# I2C_Line_Sensor.net
KiCad netlist of a schematic drawn in EAGLE
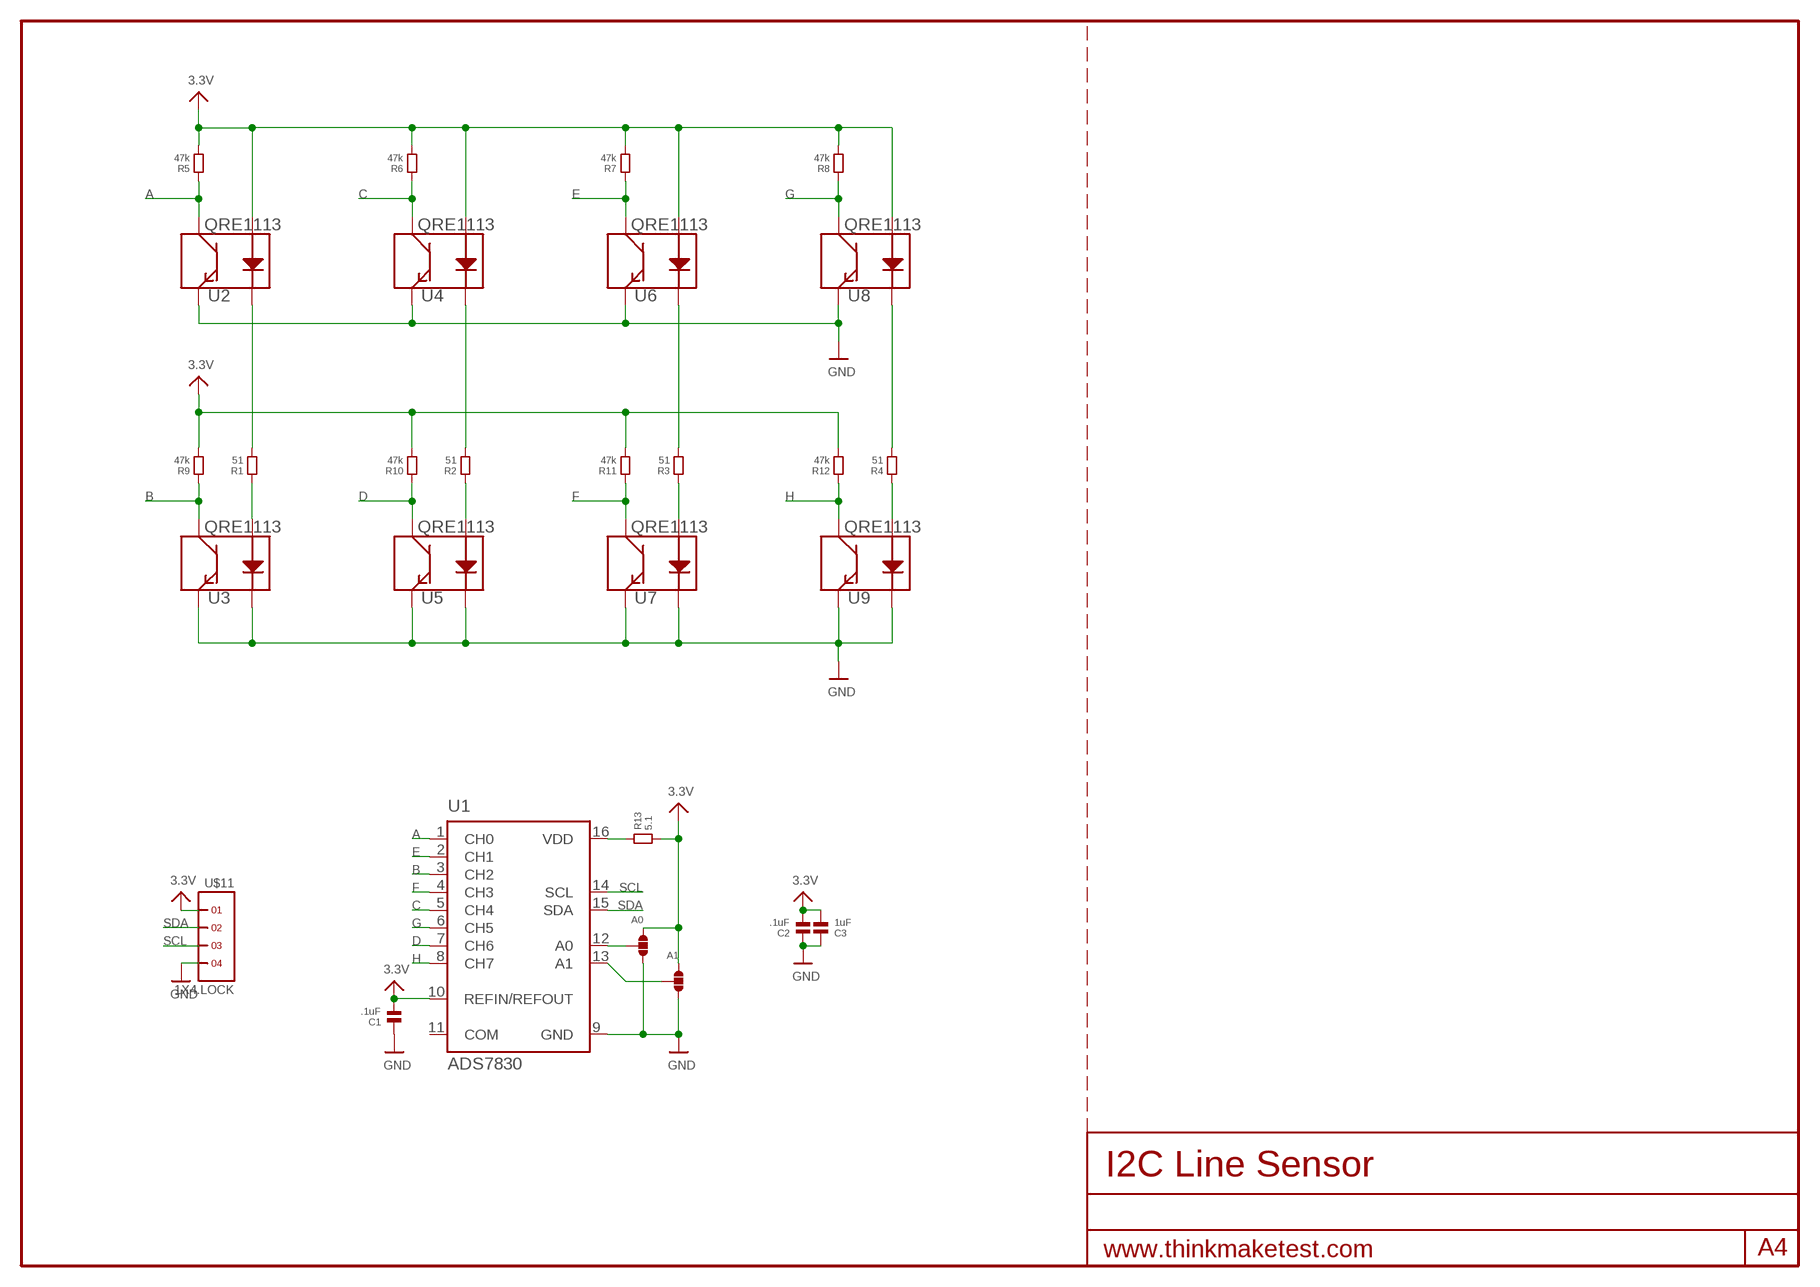
[diagram p0: schematic, sheet 1]

(export (version "E")
  (design (tool "Eeschema 10.0.6"))
  (components
    (comp (ref "A0")
      (value "SOLDERJUMPER.3.LRG.23")
      (footprint "eagle-import:3.LRG.23")
      (libsource (lib "eagle-import") (part "SOLDERJUMPER.3.LRG.23"))
    )
    (comp (ref "A1")
      (value "SOLDERJUMPER.3.LRG.23")
      (footprint "eagle-import:3.LRG.23")
      (libsource (lib "eagle-import") (part "SOLDERJUMPER.3.LRG.23"))
    )
    (comp (ref "C1")
      (value ".1uF")
      (footprint "eagle-import:0603")
      (libsource (lib "eagle-import") (part "CAPACITOR.0603"))
    )
    (comp (ref "C2")
      (value ".1uF")
      (footprint "eagle-import:0603")
      (libsource (lib "eagle-import") (part "CAPACITOR.0603"))
    )
    (comp (ref "C3")
      (value "1uF")
      (footprint "eagle-import:0603")
      (libsource (lib "eagle-import") (part "CAPACITOR.0603"))
    )
    (comp (ref "R1")
      (value "51")
      (footprint "eagle-import:0603")
      (libsource (lib "eagle-import") (part "RESISTOR.0603"))
    )
    (comp (ref "R2")
      (value "51")
      (footprint "eagle-import:0603")
      (libsource (lib "eagle-import") (part "RESISTOR.0603"))
    )
    (comp (ref "R3")
      (value "51")
      (footprint "eagle-import:0603")
      (libsource (lib "eagle-import") (part "RESISTOR.0603"))
    )
    (comp (ref "R4")
      (value "51")
      (footprint "eagle-import:0603")
      (libsource (lib "eagle-import") (part "RESISTOR.0603"))
    )
    (comp (ref "R5")
      (value "47k")
      (footprint "eagle-import:0603")
      (libsource (lib "eagle-import") (part "RESISTOR.0603"))
    )
    (comp (ref "R6")
      (value "47k")
      (footprint "eagle-import:0603")
      (libsource (lib "eagle-import") (part "RESISTOR.0603"))
    )
    (comp (ref "R7")
      (value "47k")
      (footprint "eagle-import:0603")
      (libsource (lib "eagle-import") (part "RESISTOR.0603"))
    )
    (comp (ref "R8")
      (value "47k")
      (footprint "eagle-import:0603")
      (libsource (lib "eagle-import") (part "RESISTOR.0603"))
    )
    (comp (ref "R9")
      (value "47k")
      (footprint "eagle-import:0603")
      (libsource (lib "eagle-import") (part "RESISTOR.0603"))
    )
    (comp (ref "R10")
      (value "47k")
      (footprint "eagle-import:0603")
      (libsource (lib "eagle-import") (part "RESISTOR.0603"))
    )
    (comp (ref "R11")
      (value "47k")
      (footprint "eagle-import:0603")
      (libsource (lib "eagle-import") (part "RESISTOR.0603"))
    )
    (comp (ref "R12")
      (value "47k")
      (footprint "eagle-import:0603")
      (libsource (lib "eagle-import") (part "RESISTOR.0603"))
    )
    (comp (ref "R13")
      (value "5.1")
      (footprint "eagle-import:0603")
      (libsource (lib "eagle-import") (part "RESISTOR.0603"))
    )
    (comp (ref "U$11")
      (value "1X4.LOCK")
      (footprint "eagle-import:1X4.LOCK")
      (libsource (lib "eagle-import") (part "1X4.LOCK"))
    )
    (comp (ref "U1")
      (value "ADS7830")
      (footprint "eagle-import:TSSOP16-PW")
      (libsource (lib "eagle-import") (part "ADS7828"))
    )
    (comp (ref "U2")
      (value "QRE1113")
      (footprint "eagle-import:QRE1113")
      (libsource (lib "eagle-import") (part "QRE1113"))
    )
    (comp (ref "U3")
      (value "QRE1113")
      (footprint "eagle-import:QRE1113")
      (libsource (lib "eagle-import") (part "QRE1113"))
    )
    (comp (ref "U4")
      (value "QRE1113")
      (footprint "eagle-import:QRE1113")
      (libsource (lib "eagle-import") (part "QRE1113"))
    )
    (comp (ref "U5")
      (value "QRE1113")
      (footprint "eagle-import:QRE1113")
      (libsource (lib "eagle-import") (part "QRE1113"))
    )
    (comp (ref "U6")
      (value "QRE1113")
      (footprint "eagle-import:QRE1113")
      (libsource (lib "eagle-import") (part "QRE1113"))
    )
    (comp (ref "U7")
      (value "QRE1113")
      (footprint "eagle-import:QRE1113")
      (libsource (lib "eagle-import") (part "QRE1113"))
    )
    (comp (ref "U8")
      (value "QRE1113")
      (footprint "eagle-import:QRE1113")
      (libsource (lib "eagle-import") (part "QRE1113"))
    )
    (comp (ref "U9")
      (value "QRE1113")
      (footprint "eagle-import:QRE1113")
      (libsource (lib "eagle-import") (part "QRE1113"))
    )
  )
  (nets
    (net (code "1") (name "/A") (class "Default")
      (node (ref "R5") (pin "1") (pinfunction "1_1") (pintype "bidirectional"))
      (node (ref "U1") (pin "1") (pinfunction "CH0_1") (pintype "input"))
      (node (ref "U2") (pin "3") (pinfunction "C_3") (pintype "bidirectional"))
    )
    (net (code "2") (name "/B") (class "Default")
      (node (ref "R9") (pin "1") (pinfunction "1_1") (pintype "bidirectional"))
      (node (ref "U1") (pin "3") (pinfunction "CH2_3") (pintype "input"))
      (node (ref "U3") (pin "3") (pinfunction "C_3") (pintype "bidirectional"))
    )
    (net (code "3") (name "/C") (class "Default")
      (node (ref "R6") (pin "1") (pinfunction "1_1") (pintype "bidirectional"))
      (node (ref "U1") (pin "5") (pinfunction "CH4_5") (pintype "input"))
      (node (ref "U4") (pin "3") (pinfunction "C_3") (pintype "bidirectional"))
    )
    (net (code "4") (name "/D") (class "Default")
      (node (ref "R10") (pin "1") (pinfunction "1_1") (pintype "bidirectional"))
      (node (ref "U1") (pin "7") (pinfunction "CH6_7") (pintype "input"))
      (node (ref "U5") (pin "3") (pinfunction "C_3") (pintype "bidirectional"))
    )
    (net (code "5") (name "/E") (class "Default")
      (node (ref "R7") (pin "1") (pinfunction "1_1") (pintype "bidirectional"))
      (node (ref "U1") (pin "2") (pinfunction "CH1_2") (pintype "input"))
      (node (ref "U6") (pin "3") (pinfunction "C_3") (pintype "bidirectional"))
    )
    (net (code "6") (name "/F") (class "Default")
      (node (ref "R11") (pin "1") (pinfunction "1_1") (pintype "bidirectional"))
      (node (ref "U1") (pin "4") (pinfunction "CH3_4") (pintype "input"))
      (node (ref "U7") (pin "3") (pinfunction "C_3") (pintype "bidirectional"))
    )
    (net (code "7") (name "/G") (class "Default")
      (node (ref "R8") (pin "1") (pinfunction "1_1") (pintype "bidirectional"))
      (node (ref "U1") (pin "6") (pinfunction "CH5_6") (pintype "input"))
      (node (ref "U8") (pin "3") (pinfunction "C_3") (pintype "bidirectional"))
    )
    (net (code "8") (name "/H") (class "Default")
      (node (ref "R12") (pin "1") (pinfunction "1_1") (pintype "bidirectional"))
      (node (ref "U1") (pin "8") (pinfunction "CH7_8") (pintype "input"))
      (node (ref "U9") (pin "3") (pinfunction "C_3") (pintype "bidirectional"))
    )
    (net (code "9") (name "/SCL") (class "Default")
      (node (ref "U$11") (pin "3") (pinfunction "3_3") (pintype "bidirectional"))
      (node (ref "U1") (pin "14") (pinfunction "SCL_14") (pintype "input"))
    )
    (net (code "10") (name "/SDA") (class "Default")
      (node (ref "U$11") (pin "2") (pinfunction "2_2") (pintype "bidirectional"))
      (node (ref "U1") (pin "15") (pinfunction "SDA_15") (pintype "bidirectional"))
    )
    (net (code "11") (name "3.3V") (class "Default")
      (node (ref "A0") (pin "1") (pinfunction "1_1") (pintype "bidirectional"))
      (node (ref "A1") (pin "1") (pinfunction "1_1") (pintype "bidirectional"))
      (node (ref "C1") (pin "2") (pinfunction "2_2") (pintype "bidirectional"))
      (node (ref "C2") (pin "2") (pinfunction "2_2") (pintype "bidirectional"))
      (node (ref "C3") (pin "2") (pinfunction "2_2") (pintype "bidirectional"))
      (node (ref "R10") (pin "2") (pinfunction "2_2") (pintype "bidirectional"))
      (node (ref "R11") (pin "2") (pinfunction "2_2") (pintype "bidirectional"))
      (node (ref "R12") (pin "2") (pinfunction "2_2") (pintype "bidirectional"))
      (node (ref "R13") (pin "2") (pinfunction "2_2") (pintype "bidirectional"))
      (node (ref "R5") (pin "2") (pinfunction "2_2") (pintype "bidirectional"))
      (node (ref "R6") (pin "2") (pinfunction "2_2") (pintype "bidirectional"))
      (node (ref "R7") (pin "2") (pinfunction "2_2") (pintype "bidirectional"))
      (node (ref "R8") (pin "2") (pinfunction "2_2") (pintype "bidirectional"))
      (node (ref "R9") (pin "2") (pinfunction "2_2") (pintype "bidirectional"))
      (node (ref "U$11") (pin "1") (pinfunction "1_1") (pintype "bidirectional"))
      (node (ref "U1") (pin "10") (pinfunction "REFIN/REFOUT_10") (pintype "passive"))
      (node (ref "U2") (pin "1") (pinfunction "A_1") (pintype "bidirectional"))
      (node (ref "U4") (pin "1") (pinfunction "A_1") (pintype "bidirectional"))
      (node (ref "U6") (pin "1") (pinfunction "A_1") (pintype "bidirectional"))
      (node (ref "U8") (pin "1") (pinfunction "A_1") (pintype "bidirectional"))
    )
    (net (code "12") (name "GND") (class "Default")
      (node (ref "A0") (pin "3") (pinfunction "3_3") (pintype "bidirectional"))
      (node (ref "A1") (pin "3") (pinfunction "3_3") (pintype "bidirectional"))
      (node (ref "C1") (pin "1") (pinfunction "1_1") (pintype "bidirectional"))
      (node (ref "C2") (pin "1") (pinfunction "1_1") (pintype "bidirectional"))
      (node (ref "C3") (pin "1") (pinfunction "1_1") (pintype "bidirectional"))
      (node (ref "U$11") (pin "4") (pinfunction "4_4") (pintype "bidirectional"))
      (node (ref "U1") (pin "9") (pinfunction "GND_9") (pintype "power_in"))
      (node (ref "U2") (pin "4") (pinfunction "E_4") (pintype "bidirectional"))
      (node (ref "U3") (pin "2") (pinfunction "K_2") (pintype "bidirectional"))
      (node (ref "U3") (pin "4") (pinfunction "E_4") (pintype "bidirectional"))
      (node (ref "U4") (pin "4") (pinfunction "E_4") (pintype "bidirectional"))
      (node (ref "U5") (pin "2") (pinfunction "K_2") (pintype "bidirectional"))
      (node (ref "U5") (pin "4") (pinfunction "E_4") (pintype "bidirectional"))
      (node (ref "U6") (pin "4") (pinfunction "E_4") (pintype "bidirectional"))
      (node (ref "U7") (pin "2") (pinfunction "K_2") (pintype "bidirectional"))
      (node (ref "U7") (pin "4") (pinfunction "E_4") (pintype "bidirectional"))
      (node (ref "U8") (pin "4") (pinfunction "E_4") (pintype "bidirectional"))
      (node (ref "U9") (pin "2") (pinfunction "K_2") (pintype "bidirectional"))
      (node (ref "U9") (pin "4") (pinfunction "E_4") (pintype "bidirectional"))
    )
    (net (code "13") (name "Net-(U1-A0)") (class "Default")
      (node (ref "A0") (pin "2") (pinfunction "2_2") (pintype "bidirectional"))
      (node (ref "U1") (pin "12") (pinfunction "A0_12") (pintype "input"))
    )
    (net (code "14") (name "Net-(U1-A1)") (class "Default")
      (node (ref "A1") (pin "2") (pinfunction "2_2") (pintype "bidirectional"))
      (node (ref "U1") (pin "13") (pinfunction "A1_13") (pintype "input"))
    )
    (net (code "15") (name "Net-(U1-VDD)") (class "Default")
      (node (ref "R13") (pin "1") (pinfunction "1_1") (pintype "bidirectional"))
      (node (ref "U1") (pin "16") (pinfunction "VDD_16") (pintype "power_in"))
    )
    (net (code "16") (name "Net-(U2-K)") (class "Default")
      (node (ref "R1") (pin "2") (pinfunction "2_2") (pintype "bidirectional"))
      (node (ref "U2") (pin "2") (pinfunction "K_2") (pintype "bidirectional"))
    )
    (net (code "17") (name "Net-(U3-A)") (class "Default")
      (node (ref "R1") (pin "1") (pinfunction "1_1") (pintype "bidirectional"))
      (node (ref "U3") (pin "1") (pinfunction "A_1") (pintype "bidirectional"))
    )
    (net (code "18") (name "Net-(U4-K)") (class "Default")
      (node (ref "R2") (pin "2") (pinfunction "2_2") (pintype "bidirectional"))
      (node (ref "U4") (pin "2") (pinfunction "K_2") (pintype "bidirectional"))
    )
    (net (code "19") (name "Net-(U5-A)") (class "Default")
      (node (ref "R2") (pin "1") (pinfunction "1_1") (pintype "bidirectional"))
      (node (ref "U5") (pin "1") (pinfunction "A_1") (pintype "bidirectional"))
    )
    (net (code "20") (name "Net-(U6-K)") (class "Default")
      (node (ref "R3") (pin "2") (pinfunction "2_2") (pintype "bidirectional"))
      (node (ref "U6") (pin "2") (pinfunction "K_2") (pintype "bidirectional"))
    )
    (net (code "21") (name "Net-(U7-A)") (class "Default")
      (node (ref "R3") (pin "1") (pinfunction "1_1") (pintype "bidirectional"))
      (node (ref "U7") (pin "1") (pinfunction "A_1") (pintype "bidirectional"))
    )
    (net (code "22") (name "Net-(U8-K)") (class "Default")
      (node (ref "R4") (pin "2") (pinfunction "2_2") (pintype "bidirectional"))
      (node (ref "U8") (pin "2") (pinfunction "K_2") (pintype "bidirectional"))
    )
    (net (code "23") (name "Net-(U9-A)") (class "Default")
      (node (ref "R4") (pin "1") (pinfunction "1_1") (pintype "bidirectional"))
      (node (ref "U9") (pin "1") (pinfunction "A_1") (pintype "bidirectional"))
    )
    (net (code "24") (name "unconnected-(U1-COM-Pad11)") (class "Default")
      (node (ref "U1") (pin "11") (pinfunction "COM_11") (pintype "input"))
    )
  )
)
